# Power_PCB_double_sided.net
KiCad netlist of a schematic drawn in EAGLE
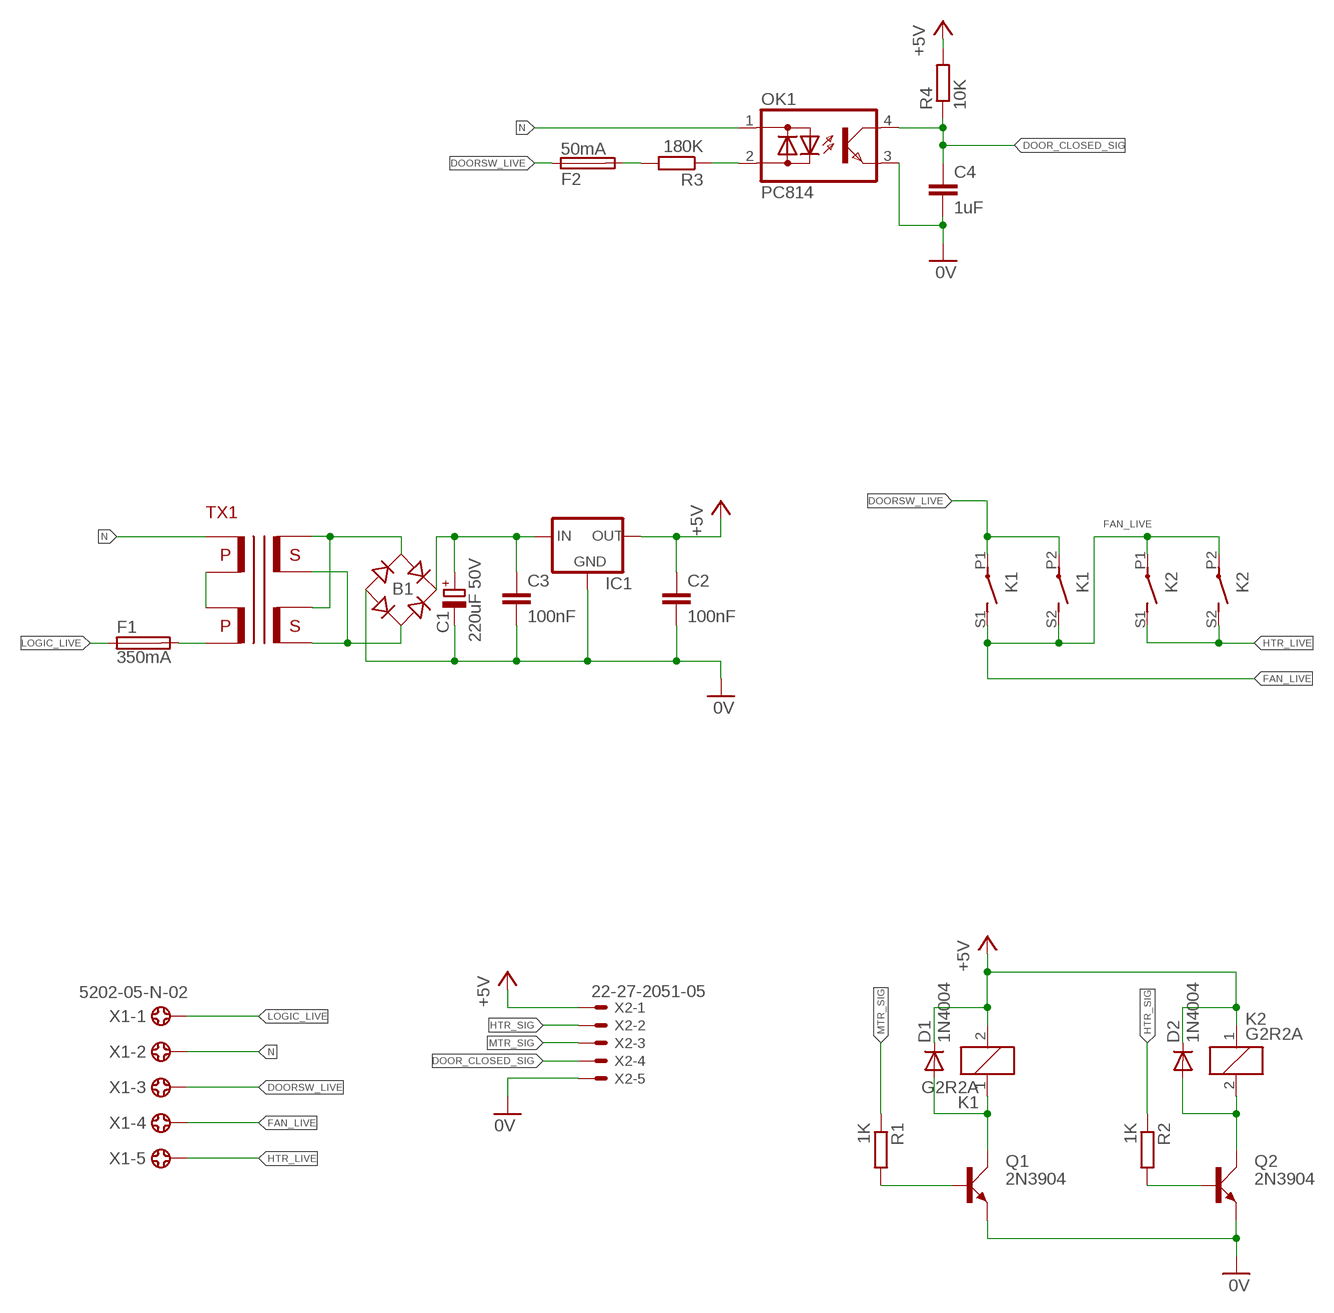
[diagram p0: schematic, sheet 1]

(export (version "E")
  (design (tool "Eeschema 10.0.6"))
  (components
    (comp (ref "B1")
      (value "RECTIFIER-RB1A")
      (footprint "eagle-import:RB1A")
      (libsource (lib "eagle-import") (part "RECTIFIER-RB1A"))
    )
    (comp (ref "C1")
      (value "220uF 50V")
      (footprint "eagle-import:E3,5-8")
      (libsource (lib "eagle-import") (part "CPOL-EUE3.5-8"))
    )
    (comp (ref "C2")
      (value "100nF")
      (footprint "eagle-import:C025-025X050")
      (libsource (lib "eagle-import") (part "C-EU025-025X050"))
    )
    (comp (ref "C3")
      (value "100nF")
      (footprint "eagle-import:C025-025X050")
      (libsource (lib "eagle-import") (part "C-EU025-025X050"))
    )
    (comp (ref "C4")
      (value "1uF")
      (footprint "eagle-import:C025-025X050")
      (libsource (lib "eagle-import") (part "C-EU025-025X050"))
    )
    (comp (ref "D1")
      (value "1N4004")
      (footprint "eagle-import:DO41-10")
      (libsource (lib "eagle-import") (part "1N4004"))
    )
    (comp (ref "D2")
      (value "1N4004")
      (footprint "eagle-import:DO41-10")
      (libsource (lib "eagle-import") (part "1N4004"))
    )
    (comp (ref "F1")
      (value "350mA")
      (footprint "eagle-import:SH25")
      (fields (field (name "MF") "SCHURTER") (field (name "MPN") "0031.8211"))
      (libsource (lib "eagle-import") (part "SH25"))
    )
    (comp (ref "F2")
      (value "50mA")
      (footprint "eagle-import:SH25")
      (fields (field (name "MF") "SCHURTER") (field (name "MPN") "0031.8211"))
      (libsource (lib "eagle-import") (part "SH25"))
    )
    (comp (ref "IC1")
      (value "V_REG_78XX-TO-220")
      (footprint "eagle-import:TO-220-ALT")
      (libsource (lib "eagle-import") (part "V_REG_78XX-TO-220"))
    )
    (comp (ref "K1")
      (value "G2R2A")
      (footprint "eagle-import:G2R2A")
      (fields (field (name "MPN") "G2R-2A-DC24"))
      (libsource (lib "eagle-import") (part "G2R2A"))
    )
    (comp (ref "K2")
      (value "G2R2A")
      (footprint "eagle-import:G2R2A")
      (fields (field (name "MPN") "G2R-2A-DC24"))
      (libsource (lib "eagle-import") (part "G2R2A"))
    )
    (comp (ref "OK1")
      (value "PC814")
      (footprint "eagle-import:DIL04")
      (libsource (lib "eagle-import") (part "PC814"))
    )
    (comp (ref "Q1")
      (value "2N3904")
      (footprint "eagle-import:TO92D")
      (libsource (lib "eagle-import") (part "2N3904"))
    )
    (comp (ref "Q2")
      (value "2N3904")
      (footprint "eagle-import:TO92D")
      (libsource (lib "eagle-import") (part "2N3904"))
    )
    (comp (ref "R1")
      (value "1K")
      (footprint "eagle-import:0207_10")
      (libsource (lib "eagle-import") (part "R-EU_0207/10"))
    )
    (comp (ref "R2")
      (value "1K")
      (footprint "eagle-import:0207_10")
      (libsource (lib "eagle-import") (part "R-EU_0207/10"))
    )
    (comp (ref "R3")
      (value "180K")
      (footprint "eagle-import:P0613V")
      (libsource (lib "eagle-import") (part "R-EU_0613/5V"))
    )
    (comp (ref "R4")
      (value "10K")
      (footprint "eagle-import:0207_10")
      (libsource (lib "eagle-import") (part "R-EU_0207/10"))
    )
    (comp (ref "TX1")
      (value "RS504-397")
      (footprint "eagle-import:RS504-397")
      (libsource (lib "eagle-import") (part "RS504-397"))
    )
    (comp (ref "X1")
      (value "5202-05-N-02")
      (footprint "eagle-import:5202-05-N-02")
      (libsource (lib "eagle-import") (part "5202-05-N-02"))
    )
    (comp (ref "X2")
      (value "22-27-2051-05")
      (footprint "eagle-import:6410-05")
      (libsource (lib "eagle-import") (part "22-?-0527-2051"))
    )
  )
  (nets
    (net (code "1") (name "+5V") (class "Default")
      (node (ref "C2") (pin "1") (pinfunction "1_1") (pintype "passive"))
      (node (ref "D1") (pin "C") (pinfunction "C_C") (pintype "passive"))
      (node (ref "D2") (pin "C") (pinfunction "C_C") (pintype "passive"))
      (node (ref "IC1") (pin "OUT") (pinfunction "OUT_OUT") (pintype "output"))
      (node (ref "K1") (pin "2") (pinfunction "2_2") (pintype "passive"))
      (node (ref "K2") (pin "1") (pinfunction "1_1") (pintype "passive"))
      (node (ref "R4") (pin "2") (pinfunction "2_2") (pintype "passive"))
      (node (ref "X2") (pin "1") (pinfunction "S_1") (pintype "passive"))
    )
    (net (code "2") (name "0V") (class "Default")
      (node (ref "B1") (pin "-") (pinfunction "-_-") (pintype "passive"))
      (node (ref "C1") (pin "-") (pinfunction "-_-") (pintype "passive"))
      (node (ref "C2") (pin "2") (pinfunction "2_2") (pintype "passive"))
      (node (ref "C3") (pin "2") (pinfunction "2_2") (pintype "passive"))
      (node (ref "C4") (pin "2") (pinfunction "2_2") (pintype "passive"))
      (node (ref "IC1") (pin "GND") (pinfunction "GND_GND") (pintype "input"))
      (node (ref "OK1") (pin "3") (pinfunction "E_3") (pintype "passive"))
      (node (ref "Q1") (pin "E") (pinfunction "E_E") (pintype "passive"))
      (node (ref "Q2") (pin "E") (pinfunction "E_E") (pintype "passive"))
      (node (ref "X2") (pin "5") (pinfunction "S_5") (pintype "passive"))
    )
    (net (code "3") (name "DOORSW_LIVE") (class "Default")
      (node (ref "F2") (pin "1") (pinfunction "1_1") (pintype "passive"))
      (node (ref "K1") (pin "P1") (pinfunction "P_P1") (pintype "passive"))
      (node (ref "K1") (pin "P2") (pinfunction "P_P2") (pintype "passive"))
      (node (ref "X1") (pin "3") (pinfunction "1_3") (pintype "passive"))
    )
    (net (code "4") (name "DOOR_CLOSED_SIG") (class "Default")
      (node (ref "C4") (pin "1") (pinfunction "1_1") (pintype "passive"))
      (node (ref "OK1") (pin "4") (pinfunction "C_4") (pintype "passive"))
      (node (ref "R4") (pin "1") (pinfunction "1_1") (pintype "passive"))
      (node (ref "X2") (pin "4") (pinfunction "S_4") (pintype "passive"))
    )
    (net (code "5") (name "FAN_LIVE") (class "Default")
      (node (ref "K1") (pin "S1") (pinfunction "S_S1") (pintype "passive"))
      (node (ref "K1") (pin "S2") (pinfunction "S_S2") (pintype "passive"))
      (node (ref "K2") (pin "P1") (pinfunction "P_P1") (pintype "passive"))
      (node (ref "K2") (pin "P2") (pinfunction "P_P2") (pintype "passive"))
      (node (ref "X1") (pin "4") (pinfunction "1_4") (pintype "passive"))
    )
    (net (code "6") (name "HTR_LIVE") (class "Default")
      (node (ref "K2") (pin "S1") (pinfunction "S_S1") (pintype "passive"))
      (node (ref "K2") (pin "S2") (pinfunction "S_S2") (pintype "passive"))
      (node (ref "X1") (pin "5") (pinfunction "1_5") (pintype "passive"))
    )
    (net (code "7") (name "HTR_SIG") (class "Default")
      (node (ref "R2") (pin "1") (pinfunction "1_1") (pintype "passive"))
      (node (ref "X2") (pin "2") (pinfunction "S_2") (pintype "passive"))
    )
    (net (code "8") (name "LOGIC_LIVE") (class "Default")
      (node (ref "F1") (pin "1") (pinfunction "1_1") (pintype "passive"))
      (node (ref "X1") (pin "1") (pinfunction "1_1") (pintype "passive"))
    )
    (net (code "9") (name "MTR_SIG") (class "Default")
      (node (ref "R1") (pin "1") (pinfunction "1_1") (pintype "passive"))
      (node (ref "X2") (pin "3") (pinfunction "S_3") (pintype "passive"))
    )
    (net (code "10") (name "N") (class "Default")
      (node (ref "OK1") (pin "1") (pinfunction "AC1_1") (pintype "passive"))
      (node (ref "TX1") (pin "115V1") (pinfunction "115V1_115V1") (pintype "bidirectional"))
      (node (ref "X1") (pin "2") (pinfunction "1_2") (pintype "passive"))
    )
    (net (code "11") (name "Net-(B1-Pad+)") (class "Default")
      (node (ref "B1") (pin "+") (pinfunction "+_+") (pintype "passive"))
      (node (ref "C1") (pin "+") (pinfunction "+_+") (pintype "passive"))
      (node (ref "C3") (pin "1") (pinfunction "1_1") (pintype "passive"))
      (node (ref "IC1") (pin "IN") (pinfunction "IN_IN") (pintype "input"))
    )
    (net (code "12") (name "Net-(B1-PadAC1)") (class "Default")
      (node (ref "B1") (pin "AC1") (pinfunction "AC1_AC1") (pintype "passive"))
      (node (ref "TX1") (pin "12V1") (pinfunction "12V1_12V1") (pintype "bidirectional"))
      (node (ref "TX1") (pin "12V2") (pinfunction "12V2_12V2") (pintype "bidirectional"))
    )
    (net (code "13") (name "Net-(B1-PadAC2)") (class "Default")
      (node (ref "B1") (pin "AC2") (pinfunction "AC2_AC2") (pintype "passive"))
      (node (ref "TX1") (pin "12V1_0") (pinfunction "12V1_0_12V1_0") (pintype "bidirectional"))
      (node (ref "TX1") (pin "12V2_0") (pinfunction "12V2_0_12V2_0") (pintype "bidirectional"))
    )
    (net (code "14") (name "Net-(D1-PadA)") (class "Default")
      (node (ref "D1") (pin "A") (pinfunction "A_A") (pintype "passive"))
      (node (ref "K1") (pin "1") (pinfunction "1_1") (pintype "passive"))
      (node (ref "Q1") (pin "C") (pinfunction "C_C") (pintype "passive"))
    )
    (net (code "15") (name "Net-(D2-PadA)") (class "Default")
      (node (ref "D2") (pin "A") (pinfunction "A_A") (pintype "passive"))
      (node (ref "K2") (pin "2") (pinfunction "2_2") (pintype "passive"))
      (node (ref "Q2") (pin "C") (pinfunction "C_C") (pintype "passive"))
    )
    (net (code "16") (name "Net-(F1-Pad2)") (class "Default")
      (node (ref "F1") (pin "2") (pinfunction "2_2") (pintype "passive"))
      (node (ref "TX1") (pin "0V2") (pinfunction "0V2_0V2") (pintype "bidirectional"))
    )
    (net (code "17") (name "Net-(F2-Pad2)") (class "Default")
      (node (ref "F2") (pin "2") (pinfunction "2_2") (pintype "passive"))
      (node (ref "R3") (pin "2") (pinfunction "2_2") (pintype "passive"))
    )
    (net (code "18") (name "Net-(OK1-AC2)") (class "Default")
      (node (ref "OK1") (pin "2") (pinfunction "AC2_2") (pintype "passive"))
      (node (ref "R3") (pin "1") (pinfunction "1_1") (pintype "passive"))
    )
    (net (code "19") (name "Net-(Q1-PadB)") (class "Default")
      (node (ref "Q1") (pin "B") (pinfunction "B_B") (pintype "passive"))
      (node (ref "R1") (pin "2") (pinfunction "2_2") (pintype "passive"))
    )
    (net (code "20") (name "Net-(Q2-PadB)") (class "Default")
      (node (ref "Q2") (pin "B") (pinfunction "B_B") (pintype "passive"))
      (node (ref "R2") (pin "2") (pinfunction "2_2") (pintype "passive"))
    )
    (net (code "21") (name "Net-(TX1-Pad0V1)") (class "Default")
      (node (ref "TX1") (pin "0V1") (pinfunction "0V1_0V1") (pintype "bidirectional"))
      (node (ref "TX1") (pin "115V2") (pinfunction "115V2_115V2") (pintype "bidirectional"))
    )
  )
)
